# eval.net
KiCad netlist of a schematic drawn in Altium Designer
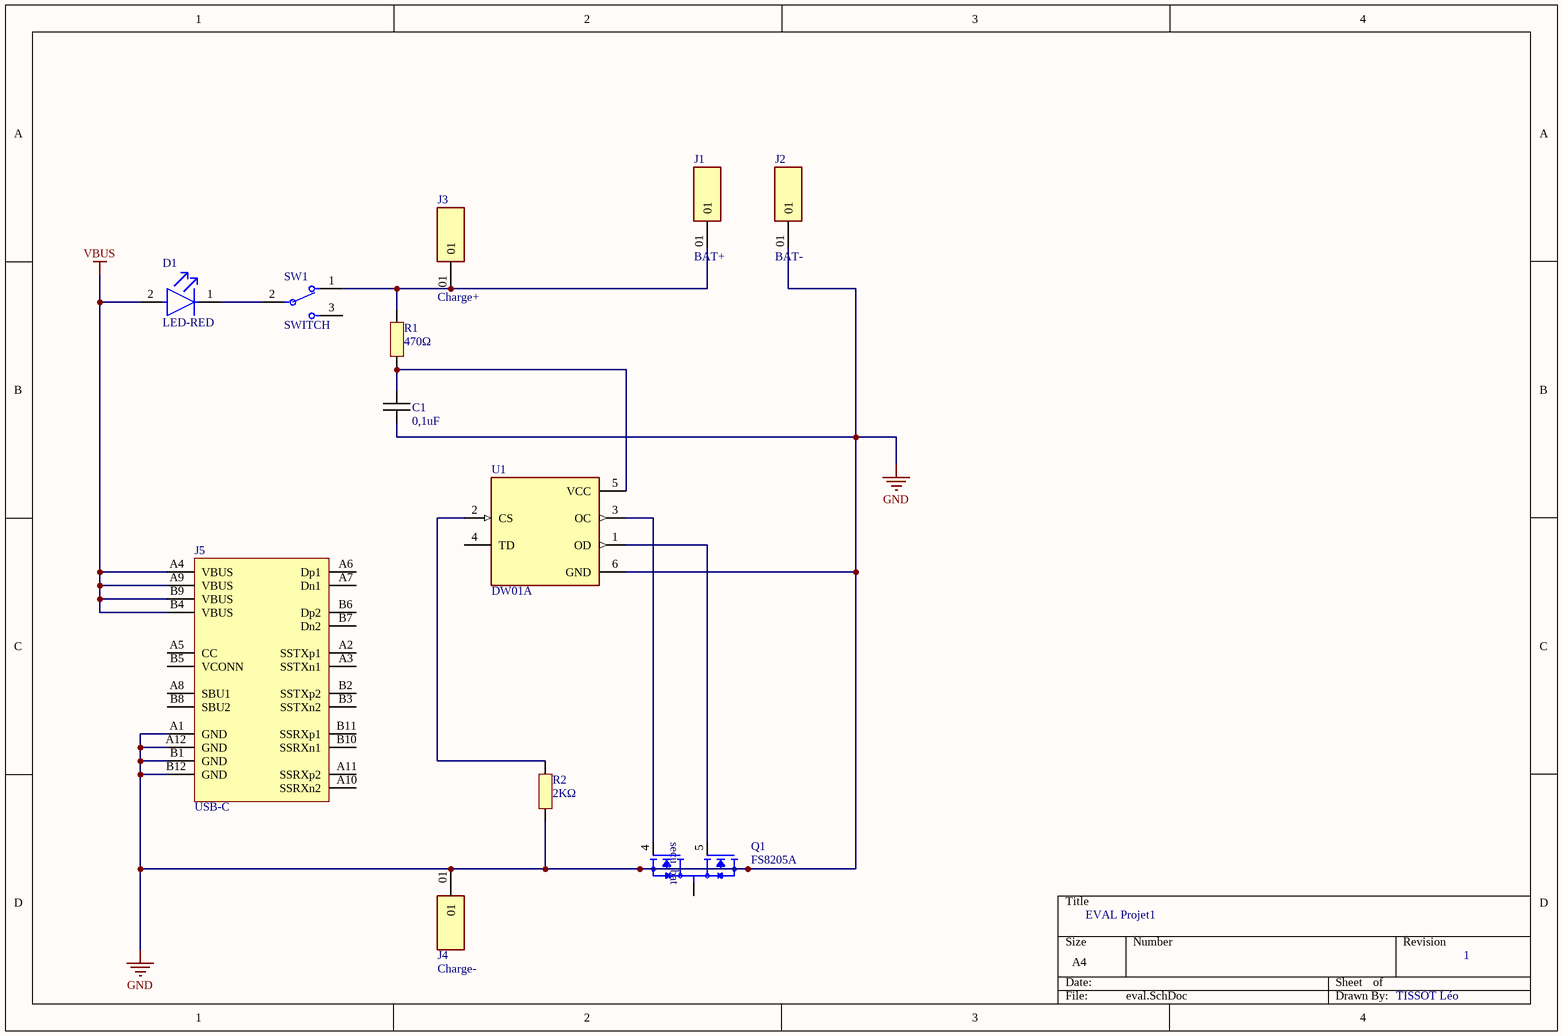
[diagram p0: eval.SchDoc]

(export (version "E")
  (design (tool "Eeschema 10.0.6"))
  (components
    (comp (ref "C1")
      (value "0,1uF")
      (footprint "SMD-1005-CAP")
      (libsource (lib "Schematic_lib") (part "CAPACITOR"))
    )
    (comp (ref "D1")
      (value "LED-RED")
      (footprint "SMD-1608-LED")
      (description "LED GREEN CLEAR CHIP SMD LTST-C190GKT")
      (fields (field (name "VOLTAGE") "2V"))
      (libsource (lib "Schematic_lib") (part "LED-RED"))
    )
    (comp (ref "J1")
      (value "BAT+")
      (footprint "HEADER")
      (description "Connector Header Through Hole 1 position")
      (fields (field (name "MF") "Samtec") (field (name "MP") "MTMM-101-05-G-S-225"))
      (libsource (lib "Schematic_lib") (part "HEADER"))
    )
    (comp (ref "J2")
      (value "BAT-")
      (footprint "HEADER")
      (description "Connector Header Through Hole 1 position")
      (fields (field (name "MF") "Samtec") (field (name "MP") "MTMM-101-05-G-S-225"))
      (libsource (lib "Schematic_lib") (part "HEADER"))
    )
    (comp (ref "J3")
      (value "Charge+")
      (footprint "HEADER")
      (description "Connector Header Through Hole 1 position")
      (fields (field (name "MF") "Samtec") (field (name "MP") "MTMM-101-05-G-S-225"))
      (libsource (lib "Schematic_lib") (part "HEADER"))
    )
    (comp (ref "J4")
      (value "Charge-")
      (footprint "HEADER")
      (description "Connector Header Through Hole 1 position")
      (fields (field (name "MF") "Samtec") (field (name "MP") "MTMM-101-05-G-S-225"))
      (libsource (lib "") (part "HEADER_1"))
    )
    (comp (ref "J5") (value "USB-C") (footprint "USB-C") (libsource (lib "Schematic_lib") (part "USB-C")))
    (comp (ref "Q1")
      (value "FS8205A")
      (footprint "FS8205A")
      (fields (field (name "MF") "Fortune Semiconductor"))
      (libsource (lib "Schematic_lib") (part "FS8205A"))
    )
    (comp (ref "R1")
      (value "470Ω")
      (footprint "SMD-1005-RES")
      (libsource (lib "Schematic_lib") (part "RESISTOR"))
    )
    (comp (ref "R2") (value "2KΩ") (footprint "SMD-1005-RES") (libsource (lib "") (part "RESISTOR_1")))
    (comp (ref "SW1")
      (value "SWITCH")
      (footprint "SMD-SWITCH")
      (description "SWITCH SLIDE SPDT 300MA 6V JS102011SCQN")
      (libsource (lib "Schematic_lib") (part "SWITCH"))
    )
    (comp (ref "U1")
      (value "DW01A")
      (footprint "DW01A")
      (description "One Cell Lithium-ion/Polymer Battery Protection IC")
      (fields (field (name "MF") "Fortune Semiconductor"))
      (libsource (lib "Schematic_lib") (part "DW01A"))
    )
  )
  (nets
    (net (code "1") (name "GND") (class "Default")
      (node (ref "C1") (pin "2") (pinfunction "2_2") (pintype "passive"))
      (node (ref "J2") (pin "01") (pinfunction "01_01") (pintype "passive"))
      (node (ref "J4") (pin "01") (pinfunction "01_01") (pintype "passive"))
      (node (ref "J5") (pin "A1") (pinfunction "GND_A1") (pintype "passive"))
      (node (ref "J5") (pin "A12") (pinfunction "GND_A12") (pintype "passive"))
      (node (ref "J5") (pin "B1") (pinfunction "GND_B1") (pintype "passive"))
      (node (ref "J5") (pin "B12") (pinfunction "GND_B12") (pintype "passive"))
      (node (ref "Q1") (pin "2") (pinfunction "S1_2") (pintype "passive"))
      (node (ref "Q1") (pin "3") (pinfunction "S1_3") (pintype "passive"))
      (node (ref "Q1") (pin "6") (pinfunction "S2_6") (pintype "passive"))
      (node (ref "Q1") (pin "7") (pinfunction "S2_7") (pintype "passive"))
      (node (ref "R2") (pin "2") (pinfunction "2_2") (pintype "passive"))
      (node (ref "U1") (pin "6") (pinfunction "GND_6") (pintype "power_in"))
    )
    (net (code "2") (name "Net-(D1-C)") (class "Default")
      (node (ref "D1") (pin "1") (pinfunction "C_1") (pintype "passive"))
      (node (ref "SW1") (pin "2") (pinfunction "C_2") (pintype "passive"))
    )
    (net (code "3") (name "Net-(J1-Pad01)") (class "Default")
      (node (ref "J1") (pin "01") (pinfunction "01_01") (pintype "passive"))
      (node (ref "J3") (pin "01") (pinfunction "01_01") (pintype "passive"))
      (node (ref "R1") (pin "2") (pinfunction "2_2") (pintype "passive"))
      (node (ref "SW1") (pin "1") (pinfunction "1_1") (pintype "passive"))
    )
    (net (code "4") (name "Net-(Q1-D12-Pad1)") (class "Default")
      (node (ref "Q1") (pin "1") (pinfunction "D12_1") (pintype "passive"))
      (node (ref "Q1") (pin "8") (pinfunction "D12_8") (pintype "passive"))
    )
    (net (code "5") (name "Net-(Q1-G1)") (class "Default")
      (node (ref "Q1") (pin "4") (pinfunction "G1_4") (pintype "passive"))
      (node (ref "U1") (pin "3") (pinfunction "OC_3") (pintype "output"))
    )
    (net (code "6") (name "Net-(Q1-G2)") (class "Default")
      (node (ref "Q1") (pin "5") (pinfunction "G2_5") (pintype "passive"))
      (node (ref "U1") (pin "1") (pinfunction "OD_1") (pintype "output"))
    )
    (net (code "7") (name "Net-(U1-CS)") (class "Default")
      (node (ref "R2") (pin "1") (pinfunction "1_1") (pintype "passive"))
      (node (ref "U1") (pin "2") (pinfunction "CS_2") (pintype "input"))
    )
    (net (code "8") (name "Net-(U1-VCC)") (class "Default")
      (node (ref "C1") (pin "1") (pinfunction "1_1") (pintype "passive"))
      (node (ref "R1") (pin "1") (pinfunction "1_1") (pintype "passive"))
      (node (ref "U1") (pin "5") (pinfunction "VCC_5") (pintype "power_in"))
    )
    (net (code "9") (name "VBUS") (class "Default")
      (node (ref "D1") (pin "2") (pinfunction "A_2") (pintype "passive"))
      (node (ref "J5") (pin "A4") (pinfunction "VBUS_A4") (pintype "passive"))
      (node (ref "J5") (pin "A9") (pinfunction "VBUS_A9") (pintype "passive"))
      (node (ref "J5") (pin "B4") (pinfunction "VBUS_B4") (pintype "passive"))
      (node (ref "J5") (pin "B9") (pinfunction "VBUS_B9") (pintype "passive"))
    )
    (net (code "10") (name "unconnected-(J5-CC-PadA5)") (class "Default")
      (node (ref "J5") (pin "A5") (pinfunction "CC_A5") (pintype "passive"))
    )
    (net (code "11") (name "unconnected-(J5-Dn1-PadA7)") (class "Default")
      (node (ref "J5") (pin "A7") (pinfunction "Dn1_A7") (pintype "passive"))
    )
    (net (code "12") (name "unconnected-(J5-Dn2-PadB7)") (class "Default")
      (node (ref "J5") (pin "B7") (pinfunction "Dn2_B7") (pintype "passive"))
    )
    (net (code "13") (name "unconnected-(J5-Dp1-PadA6)") (class "Default")
      (node (ref "J5") (pin "A6") (pinfunction "Dp1_A6") (pintype "passive"))
    )
    (net (code "14") (name "unconnected-(J5-Dp2-PadB6)") (class "Default")
      (node (ref "J5") (pin "B6") (pinfunction "Dp2_B6") (pintype "passive"))
    )
    (net (code "15") (name "unconnected-(J5-SBU1-PadA8)") (class "Default")
      (node (ref "J5") (pin "A8") (pinfunction "SBU1_A8") (pintype "passive"))
    )
    (net (code "16") (name "unconnected-(J5-SBU2-PadB8)") (class "Default")
      (node (ref "J5") (pin "B8") (pinfunction "SBU2_B8") (pintype "passive"))
    )
    (net (code "17") (name "unconnected-(J5-SSRXn1-PadB10)") (class "Default")
      (node (ref "J5") (pin "B10") (pinfunction "SSRXn1_B10") (pintype "passive"))
    )
    (net (code "18") (name "unconnected-(J5-SSRXn2-PadA10)") (class "Default")
      (node (ref "J5") (pin "A10") (pinfunction "SSRXn2_A10") (pintype "passive"))
    )
    (net (code "19") (name "unconnected-(J5-SSRXp1-PadB11)") (class "Default")
      (node (ref "J5") (pin "B11") (pinfunction "SSRXp1_B11") (pintype "passive"))
    )
    (net (code "20") (name "unconnected-(J5-SSRXp2-PadA11)") (class "Default")
      (node (ref "J5") (pin "A11") (pinfunction "SSRXp2_A11") (pintype "passive"))
    )
    (net (code "21") (name "unconnected-(J5-SSTXn1-PadA3)") (class "Default")
      (node (ref "J5") (pin "A3") (pinfunction "SSTXn1_A3") (pintype "passive"))
    )
    (net (code "22") (name "unconnected-(J5-SSTXn2-PadB3)") (class "Default")
      (node (ref "J5") (pin "B3") (pinfunction "SSTXn2_B3") (pintype "passive"))
    )
    (net (code "23") (name "unconnected-(J5-SSTXp1-PadA2)") (class "Default")
      (node (ref "J5") (pin "A2") (pinfunction "SSTXp1_A2") (pintype "passive"))
    )
    (net (code "24") (name "unconnected-(J5-SSTXp2-PadB2)") (class "Default")
      (node (ref "J5") (pin "B2") (pinfunction "SSTXp2_B2") (pintype "passive"))
    )
    (net (code "25") (name "unconnected-(J5-VCONN-PadB5)") (class "Default")
      (node (ref "J5") (pin "B5") (pinfunction "VCONN_B5") (pintype "passive"))
    )
    (net (code "26") (name "unconnected-(SW1-Pad3)") (class "Default")
      (node (ref "SW1") (pin "3") (pinfunction "3_3") (pintype "passive"))
    )
    (net (code "27") (name "unconnected-(U1-TD-Pad4)") (class "Default")
      (node (ref "U1") (pin "4") (pinfunction "TD_4") (pintype "passive"))
    )
  )
)
